# 2_POWER.net
KiCad netlist of a schematic drawn in Altium Designer
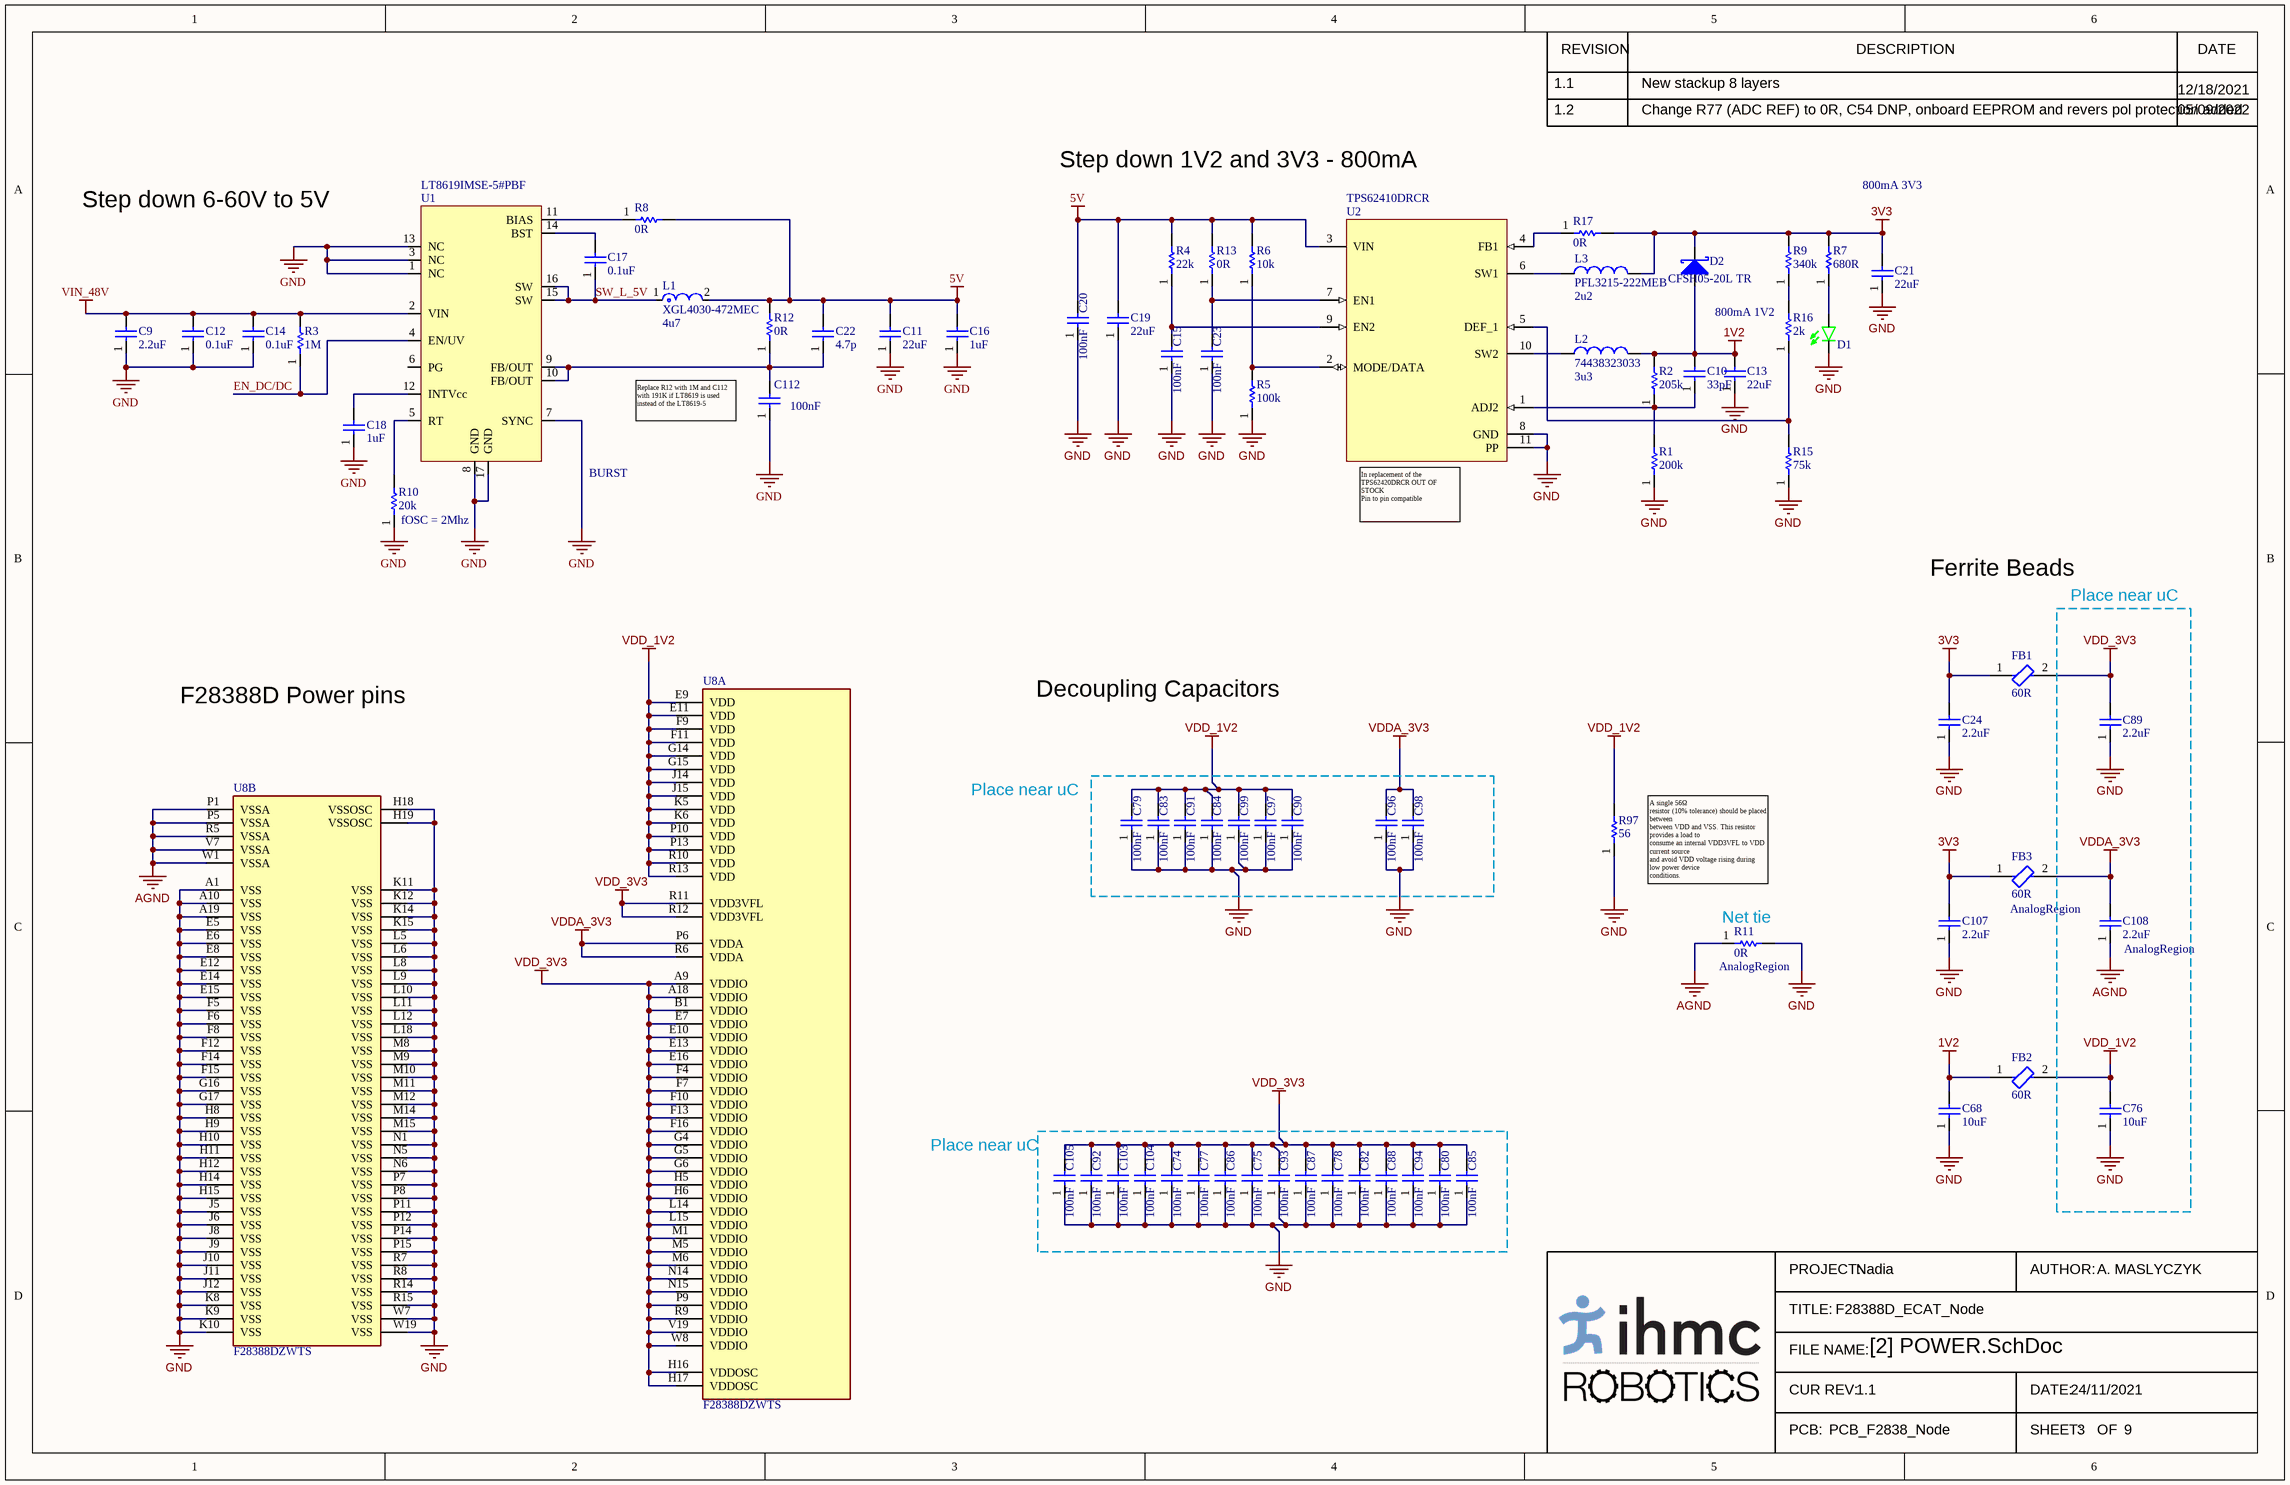
[diagram p0: [2] POWER.SchDoc]

(export (version "E")
  (design (tool "Eeschema 10.0.6"))
  (components
    (comp (ref "C9")
      (value "2.2uF")
      (footprint "CAPC3216X16N(1206)")
      (description "CAP CER 2.2UF 100V X7S 1206")
      (fields (field (name "MPN") "C3216X7S2A225K160AB") (field (name "TOLERANCE") "10%"))
      (libsource (lib "IHMC_Altium_Lib") (part "2.2uF_100V_1206_Cap"))
    )
    (comp (ref "C10")
      (value "33pF")
      (footprint "0402_C")
      (description "Cap, Mlcc, Np0, 33Pf, 25V, 0402 Rohs Compliant: Yes")
      (fields
        (field (name "MANUFACTURER") "Wurth Electronics")
        (field (name "MANUFACTURER PART NUMBER") "885012005043")
      )
      (libsource (lib "IHMC_Altium_Lib") (part "33pF_25V_5%_C0G_0402_885012005043_CAP"))
    )
    (comp (ref "C11")
      (value "22uF")
      (footprint "CAPC1608X09N(0603)")
      (description "CAP CER 22UF 10V X5R 0603")
      (fields (field (name "MPN") "C1608X5R1A226M080AC") (field (name "TOLERANCE") "20%"))
      (libsource (lib "IHMC_Altium_Lib") (part "22uF_10V_0603_CAP"))
    )
    (comp (ref "C12")
      (value "0.1uF")
      (footprint "CAPC1608X09N(0603)")
      (description "CAP CER 0.1UF 100V X7R 0603")
      (fields (field (name "MPN") "CL10B104KC8NNNC") (field (name "TOLERANCE") "10%"))
      (libsource (lib "IHMC_Altium_Lib") (part "0.1uF_100V_0603_CAP"))
    )
    (comp (ref "C13")
      (value "22uF")
      (footprint "CAPC1608X09N(0603)")
      (description "CAP CER 22UF 10V X5R 0603")
      (fields (field (name "MPN") "C1608X5R1A226M080AC") (field (name "TOLERANCE") "20%"))
      (libsource (lib "IHMC_Altium_Lib") (part "22uF_10V_0603_CAP"))
    )
    (comp (ref "C14")
      (value "0.1uF")
      (footprint "CAPC1608X09N(0603)")
      (description "CAP CER 0.1UF 100V X7R 0603")
      (fields (field (name "MPN") "CL10B104KC8NNNC") (field (name "TOLERANCE") "10%"))
      (libsource (lib "IHMC_Altium_Lib") (part "0.1uF_100V_0603_CAP"))
    )
    (comp (ref "C15")
      (value "100nF")
      (footprint "CAPC1005X03N(0402)")
      (description "CAP CER 0.1UF 16V X7R 0402")
      (fields (field (name "MPN") "GRM155R71C104JA88D") (field (name "TOLERANCE") "5%"))
      (libsource (lib "IHMC_Altium_Lib") (part "100nF_16V_0402_CAP"))
    )
    (comp (ref "C16")
      (value "1uF")
      (footprint "CAPC1608X09N(0603)")
      (description "MLCC - SMD/SMT 25volts 1uF X5R 10%")
      (fields
        (field (name "MPN") "C0603C105K3PACTU")
        (field (name "VOLTAGE") "25VDC")
        (field (name "DRAWN BY") "TC")
      )
      (libsource (lib "IHMC_Altium_Lib") (part "1uF_25VDC_0603_Cap"))
    )
    (comp (ref "C17")
      (value "0.1uF")
      (footprint "CAPC1608X09N(0603)")
      (description "CAP CER 0.1UF 100V X7R 0603")
      (fields (field (name "MPN") "CL10B104KC8NNNC") (field (name "TOLERANCE") "10%"))
      (libsource (lib "IHMC_Altium_Lib") (part "0.1uF_100V_0603_CAP"))
    )
    (comp (ref "C18")
      (value "1uF")
      (footprint "CAPC1608X09N(0603)")
      (description "MLCC - SMD/SMT 25volts 1uF X5R 10%")
      (fields
        (field (name "MPN") "C0603C105K3PACTU")
        (field (name "VOLTAGE") "25VDC")
        (field (name "DRAWN BY") "TC")
      )
      (libsource (lib "IHMC_Altium_Lib") (part "1uF_25VDC_0603_Cap"))
    )
    (comp (ref "C19")
      (value "22uF")
      (footprint "CAPC1608X09N(0603)")
      (description "CAP CER 22UF 10V X5R 0603")
      (fields (field (name "MPN") "C1608X5R1A226M080AC") (field (name "TOLERANCE") "20%"))
      (libsource (lib "IHMC_Altium_Lib") (part "22uF_10V_0603_CAP"))
    )
    (comp (ref "C20")
      (value "100nF")
      (footprint "CAPC1005X03N(0402)")
      (description "CAP CER 0.1UF 16V X7R 0402")
      (fields (field (name "MPN") "GRM155R71C104JA88D") (field (name "TOLERANCE") "5%"))
      (libsource (lib "IHMC_Altium_Lib") (part "100nF_16V_0402_CAP"))
    )
    (comp (ref "C21")
      (value "22uF")
      (footprint "CAPC1608X09N(0603)")
      (description "CAP CER 22UF 10V X5R 0603")
      (fields (field (name "MPN") "C1608X5R1A226M080AC") (field (name "TOLERANCE") "20%"))
      (libsource (lib "IHMC_Altium_Lib") (part "22uF_10V_0603_CAP"))
    )
    (comp (ref "C22")
      (value "4.7p")
      (footprint "0402_C")
      (fields
        (field (name "MANUFACTURER") "TDK")
        (field (name "MANUFACTURER PART NUMBER") "CGA2B2C0G1H4R7C050BA")
      )
      (libsource (lib "IHMC_Altium_Lib") (part "4p7_0402_50V_C0G_  CGA2B2C0G1H4R7C050BA"))
    )
    (comp (ref "C23")
      (value "100nF")
      (footprint "CAPC1005X03N(0402)")
      (description "CAP CER 0.1UF 16V X7R 0402")
      (fields (field (name "MPN") "GRM155R71C104JA88D") (field (name "TOLERANCE") "5%"))
      (libsource (lib "IHMC_Altium_Lib") (part "100nF_16V_0402_CAP"))
    )
    (comp (ref "C24")
      (value "2.2uF")
      (footprint "CAPC1608X09N(0603)")
      (description "CAP CER 2.2UF 10V X5R 0603")
      (fields (field (name "MPN") "GRM188R61A225KE34D") (field (name "TOLERANCE") "10%"))
      (libsource (lib "IHMC_Altium_Lib") (part "2.2uF_10V_0603_CAP"))
    )
    (comp (ref "C68")
      (value "10uF")
      (footprint "CAPC1608X09N(0603)")
      (description "CAP CER 10UF 16V X6S 0603")
      (fields (field (name "MPN") "CL10X106MO8NRNC") (field (name "TOLERANCE") "20%"))
      (libsource (lib "IHMC_Altium_Lib") (part "10uF_16V_0603_CAP"))
    )
    (comp (ref "C74")
      (value "100nF")
      (footprint "CAPC1005X03N(0402)")
      (description "CAP CER 0.1UF 16V X7R 0402")
      (fields (field (name "MPN") "GRM155R71C104JA88D") (field (name "TOLERANCE") "5%"))
      (libsource (lib "IHMC_Altium_Lib") (part "100nF_16V_0402_CAP"))
    )
    (comp (ref "C75")
      (value "100nF")
      (footprint "CAPC1005X03N(0402)")
      (description "CAP CER 0.1UF 16V X7R 0402")
      (fields (field (name "MPN") "GRM155R71C104JA88D") (field (name "TOLERANCE") "5%"))
      (libsource (lib "IHMC_Altium_Lib") (part "100nF_16V_0402_CAP"))
    )
    (comp (ref "C76")
      (value "10uF")
      (footprint "CAPC1608X09N(0603)")
      (description "CAP CER 10UF 16V X6S 0603")
      (fields (field (name "MPN") "CL10X106MO8NRNC") (field (name "TOLERANCE") "20%"))
      (libsource (lib "IHMC_Altium_Lib") (part "10uF_16V_0603_CAP"))
    )
    (comp (ref "C77")
      (value "100nF")
      (footprint "CAPC1005X03N(0402)")
      (description "CAP CER 0.1UF 16V X7R 0402")
      (fields (field (name "MPN") "GRM155R71C104JA88D") (field (name "TOLERANCE") "5%"))
      (libsource (lib "IHMC_Altium_Lib") (part "100nF_16V_0402_CAP"))
    )
    (comp (ref "C78")
      (value "100nF")
      (footprint "CAPC1005X03N(0402)")
      (description "CAP CER 0.1UF 16V X7R 0402")
      (fields (field (name "MPN") "GRM155R71C104JA88D") (field (name "TOLERANCE") "5%"))
      (libsource (lib "IHMC_Altium_Lib") (part "100nF_16V_0402_CAP"))
    )
    (comp (ref "C79")
      (value "100nF")
      (footprint "CAPC1005X03N(0402)")
      (description "CAP CER 0.1UF 16V X7R 0402")
      (fields (field (name "MPN") "GRM155R71C104JA88D") (field (name "TOLERANCE") "5%"))
      (libsource (lib "IHMC_Altium_Lib") (part "100nF_16V_0402_CAP"))
    )
    (comp (ref "C80")
      (value "100nF")
      (footprint "CAPC1005X03N(0402)")
      (description "CAP CER 0.1UF 16V X7R 0402")
      (fields (field (name "MPN") "GRM155R71C104JA88D") (field (name "TOLERANCE") "5%"))
      (libsource (lib "IHMC_Altium_Lib") (part "100nF_16V_0402_CAP"))
    )
    (comp (ref "C82")
      (value "100nF")
      (footprint "CAPC1005X03N(0402)")
      (description "CAP CER 0.1UF 16V X7R 0402")
      (fields (field (name "MPN") "GRM155R71C104JA88D") (field (name "TOLERANCE") "5%"))
      (libsource (lib "IHMC_Altium_Lib") (part "100nF_16V_0402_CAP"))
    )
    (comp (ref "C83")
      (value "100nF")
      (footprint "CAPC1005X03N(0402)")
      (description "CAP CER 0.1UF 16V X7R 0402")
      (fields (field (name "MPN") "GRM155R71C104JA88D") (field (name "TOLERANCE") "5%"))
      (libsource (lib "IHMC_Altium_Lib") (part "100nF_16V_0402_CAP"))
    )
    (comp (ref "C84")
      (value "100nF")
      (footprint "CAPC1005X03N(0402)")
      (description "CAP CER 0.1UF 16V X7R 0402")
      (fields (field (name "MPN") "GRM155R71C104JA88D") (field (name "TOLERANCE") "5%"))
      (libsource (lib "IHMC_Altium_Lib") (part "100nF_16V_0402_CAP"))
    )
    (comp (ref "C85")
      (value "100nF")
      (footprint "CAPC1005X03N(0402)")
      (description "CAP CER 0.1UF 16V X7R 0402")
      (fields (field (name "MPN") "GRM155R71C104JA88D") (field (name "TOLERANCE") "5%"))
      (libsource (lib "IHMC_Altium_Lib") (part "100nF_16V_0402_CAP"))
    )
    (comp (ref "C86")
      (value "100nF")
      (footprint "CAPC1005X03N(0402)")
      (description "CAP CER 0.1UF 16V X7R 0402")
      (fields (field (name "MPN") "GRM155R71C104JA88D") (field (name "TOLERANCE") "5%"))
      (libsource (lib "IHMC_Altium_Lib") (part "100nF_16V_0402_CAP"))
    )
    (comp (ref "C87")
      (value "100nF")
      (footprint "CAPC1005X03N(0402)")
      (description "CAP CER 0.1UF 16V X7R 0402")
      (fields (field (name "MPN") "GRM155R71C104JA88D") (field (name "TOLERANCE") "5%"))
      (libsource (lib "IHMC_Altium_Lib") (part "100nF_16V_0402_CAP"))
    )
    (comp (ref "C88")
      (value "100nF")
      (footprint "CAPC1005X03N(0402)")
      (description "CAP CER 0.1UF 16V X7R 0402")
      (fields (field (name "MPN") "GRM155R71C104JA88D") (field (name "TOLERANCE") "5%"))
      (libsource (lib "IHMC_Altium_Lib") (part "100nF_16V_0402_CAP"))
    )
    (comp (ref "C89")
      (value "2.2uF")
      (footprint "CAPC1608X09N(0603)")
      (description "CAP CER 2.2UF 10V X5R 0603")
      (fields (field (name "MPN") "GRM188R61A225KE34D") (field (name "TOLERANCE") "10%"))
      (libsource (lib "IHMC_Altium_Lib") (part "2.2uF_10V_0603_CAP"))
    )
    (comp (ref "C90")
      (value "100nF")
      (footprint "CAPC1005X03N(0402)")
      (description "CAP CER 0.1UF 16V X7R 0402")
      (fields (field (name "MPN") "GRM155R71C104JA88D") (field (name "TOLERANCE") "5%"))
      (libsource (lib "IHMC_Altium_Lib") (part "100nF_16V_0402_CAP"))
    )
    (comp (ref "C91")
      (value "100nF")
      (footprint "CAPC1005X03N(0402)")
      (description "CAP CER 0.1UF 16V X7R 0402")
      (fields (field (name "MPN") "GRM155R71C104JA88D") (field (name "TOLERANCE") "5%"))
      (libsource (lib "IHMC_Altium_Lib") (part "100nF_16V_0402_CAP"))
    )
    (comp (ref "C92")
      (value "100nF")
      (footprint "CAPC1005X03N(0402)")
      (description "CAP CER 0.1UF 16V X7R 0402")
      (fields (field (name "MPN") "GRM155R71C104JA88D") (field (name "TOLERANCE") "5%"))
      (libsource (lib "IHMC_Altium_Lib") (part "100nF_16V_0402_CAP"))
    )
    (comp (ref "C93")
      (value "100nF")
      (footprint "CAPC1005X03N(0402)")
      (description "CAP CER 0.1UF 16V X7R 0402")
      (fields (field (name "MPN") "GRM155R71C104JA88D") (field (name "TOLERANCE") "5%"))
      (libsource (lib "IHMC_Altium_Lib") (part "100nF_16V_0402_CAP"))
    )
    (comp (ref "C94")
      (value "100nF")
      (footprint "CAPC1005X03N(0402)")
      (description "CAP CER 0.1UF 16V X7R 0402")
      (fields (field (name "MPN") "GRM155R71C104JA88D") (field (name "TOLERANCE") "5%"))
      (libsource (lib "IHMC_Altium_Lib") (part "100nF_16V_0402_CAP"))
    )
    (comp (ref "C96")
      (value "100nF")
      (footprint "CAPC1005X03N(0402)")
      (description "CAP CER 0.1UF 16V X7R 0402")
      (fields (field (name "MPN") "GRM155R71C104JA88D") (field (name "TOLERANCE") "5%"))
      (libsource (lib "IHMC_Altium_Lib") (part "100nF_16V_0402_CAP"))
    )
    (comp (ref "C97")
      (value "100nF")
      (footprint "CAPC1005X03N(0402)")
      (description "CAP CER 0.1UF 16V X7R 0402")
      (fields (field (name "MPN") "GRM155R71C104JA88D") (field (name "TOLERANCE") "5%"))
      (libsource (lib "IHMC_Altium_Lib") (part "100nF_16V_0402_CAP"))
    )
    (comp (ref "C98")
      (value "100nF")
      (footprint "CAPC1005X03N(0402)")
      (description "CAP CER 0.1UF 16V X7R 0402")
      (fields (field (name "MPN") "GRM155R71C104JA88D") (field (name "TOLERANCE") "5%"))
      (libsource (lib "IHMC_Altium_Lib") (part "100nF_16V_0402_CAP"))
    )
    (comp (ref "C99")
      (value "100nF")
      (footprint "CAPC1005X03N(0402)")
      (description "CAP CER 0.1UF 16V X7R 0402")
      (fields (field (name "MPN") "GRM155R71C104JA88D") (field (name "TOLERANCE") "5%"))
      (libsource (lib "IHMC_Altium_Lib") (part "100nF_16V_0402_CAP"))
    )
    (comp (ref "C103")
      (value "100nF")
      (footprint "CAPC1005X03N(0402)")
      (description "CAP CER 0.1UF 16V X7R 0402")
      (fields (field (name "MPN") "GRM155R71C104JA88D") (field (name "TOLERANCE") "5%"))
      (libsource (lib "IHMC_Altium_Lib") (part "100nF_16V_0402_CAP"))
    )
    (comp (ref "C104")
      (value "100nF")
      (footprint "CAPC1005X03N(0402)")
      (description "CAP CER 0.1UF 16V X7R 0402")
      (fields (field (name "MPN") "GRM155R71C104JA88D") (field (name "TOLERANCE") "5%"))
      (libsource (lib "IHMC_Altium_Lib") (part "100nF_16V_0402_CAP"))
    )
    (comp (ref "C105")
      (value "100nF")
      (footprint "CAPC1005X03N(0402)")
      (description "CAP CER 0.1UF 16V X7R 0402")
      (fields (field (name "MPN") "GRM155R71C104JA88D") (field (name "TOLERANCE") "5%"))
      (libsource (lib "IHMC_Altium_Lib") (part "100nF_16V_0402_CAP"))
    )
    (comp (ref "C107")
      (value "2.2uF")
      (footprint "CAPC1608X09N(0603)")
      (description "CAP CER 2.2UF 10V X5R 0603")
      (fields (field (name "MPN") "GRM188R61A225KE34D") (field (name "TOLERANCE") "10%"))
      (libsource (lib "IHMC_Altium_Lib") (part "2.2uF_10V_0603_CAP"))
    )
    (comp (ref "C108")
      (value "2.2uF")
      (footprint "CAPC1608X09N(0603)")
      (description "CAP CER 2.2UF 10V X5R 0603")
      (fields
        (field (name "MPN") "GRM188R61A225KE34D")
        (field (name "TOLERANCE") "10%")
        (field (name "CLASSNAME") "AnalogRegion")
      )
      (libsource (lib "IHMC_Altium_Lib") (part "2.2uF_10V_0603_CAP"))
    )
    (comp (ref "C112")
      (value "100nF")
      (footprint "CAPC1005X03N(0402)")
      (description "CAP CER 0.1UF 16V X7R 0402")
      (fields (field (name "TOLERANCE") "5%") (field (name "MPN") "GRM155R71C104JA88D"))
      (libsource (lib "IHMC_Altium_Lib") (part "100nF_16V_0402_CAP"))
    )
    (comp (ref "D1")
      (value "LTST-C193KGKT-5A")
      (footprint "LEDC1608X07N(0603)")
      (description "LED GREEN CLEAR CHIP SMD")
      (fields (field (name "DRAWN BY") "TC"))
      (libsource (lib "IHMC_Altium_Lib") (part "GREEN_LED_0603"))
    )
    (comp (ref "D2")
      (value "CFSH05-20L TR")
      (footprint "SOD-882")
      (description "Silicon SCHOTTKY Diode Low Forward Voltage 20V 3A 2-Pin SOD-882L Surface Mount T/R")
      (fields (field (name "MANUFACTURER") "Central Semiconductor"))
      (libsource (lib "IHMC_Altium_Lib") (part "CFSH05-20L TR_SCHOTTKY_20V_500mA_SOD882_DIODE"))
    )
    (comp (ref "FB1")
      (value "BKP2125HS600-T")
      (footprint "FP-BKP2125-IPC_C")
      (fields
        (field (name "TOLERANCE") "25%")
        (field (name "MANUFACTURER") "Taiyo Yuden")
        (field (name "IMPEDANCE") "60R")
      )
      (libsource (lib "IHMC_Altium_Lib") (part "60R_100Mhz_0805_3A"))
    )
    (comp (ref "FB2")
      (value "BKP2125HS600-T")
      (footprint "FP-BKP2125-IPC_C")
      (fields
        (field (name "TOLERANCE") "25%")
        (field (name "MANUFACTURER") "Taiyo Yuden")
        (field (name "IMPEDANCE") "60R")
      )
      (libsource (lib "IHMC_Altium_Lib") (part "60R_100Mhz_0805_3A"))
    )
    (comp (ref "FB3")
      (value "BKP2125HS600-T")
      (footprint "FP-BKP2125-IPC_C")
      (fields
        (field (name "TOLERANCE") "25%")
        (field (name "MANUFACTURER") "Taiyo Yuden")
        (field (name "IMPEDANCE") "60R")
        (field (name "CLASSNAME") "AnalogRegion")
      )
      (libsource (lib "IHMC_Altium_Lib") (part "60R_100Mhz_0805_3A"))
    )
    (comp (ref "L1")
      (value "XGL4030-472MEC")
      (footprint "FP-XGL4030-472MEC-MFG")
      (description "Inductor Power Shielded Wirewound 4.7uH 20% 1MHz Composite 6.6A 31.5mOhm DCR Automotive T/R")
      (fields (field (name "ALTIUM_VALUE") "4u7") (field (name "MPN") "XGL4030-472"))
      (libsource (lib "IHMC_Altium_Lib") (part "XGL4030-472MEC_4u7_2A1_IND"))
    )
    (comp (ref "L2")
      (value "74438323033")
      (footprint "SMD 2510")
      (description "Inductor Power Shielded Wirewound 3.3uH 20% 100KHz Powdered Iron 1.25A 264mOhm DCR 1008 T/R")
      (fields
        (field (name "MANUFACTURER") "Wurth Electronics")
        (field (name "TOLERANCE") "20%")
        (field (name "ALTIUM_VALUE") "3u3")
      )
      (libsource (lib "IHMC_Altium_Lib") (part "3.3uH_1.25A_2520_IND"))
    )
    (comp (ref "L3")
      (value "PFL3215-222MEB")
      (footprint "1206_L")
      (description "Power inductor, shielded, 20% tol, SMT, RoHS, halogen-f")
      (fields
        (field (name "MANUFACTURER") "Coilcraft")
        (field (name "TOLERANCE") "20%")
        (field (name "ALTIUM_VALUE") "2u2")
      )
      (libsource (lib "IHMC_Altium_Lib") (part "2.2uH_1.4A_1206_PFL3215-222MEB_IND"))
    )
    (comp (ref "R1")
      (value "200k")
      (footprint "0402")
      (description "Res Thick Film 0402 200K Ohm 1% 1/10W ±100ppm/¦C SMD Punched Carrier T/R")
      (fields
        (field (name "MANUFACTURER") "Panasonic")
        (field (name "MANUFACTURER PART NUMBER") "ERJ-2RKF2003X")
      )
      (libsource (lib "IHMC_Altium_Lib") (part "200k_0402_1%_ERJ-2RKF2003X_RES"))
    )
    (comp (ref "R2")
      (value "205k")
      (footprint "0402")
      (description "Res Thick Film 0402 205K Ohm 1% 1/16W ±100ppm/°C Molded SMD SMD Paper T/R")
      (fields
        (field (name "MANUFACTURER") "Vishay")
        (field (name "MANUFACTURER PART NUMBER") "CRCW0402205KFKED")
      )
      (libsource (lib "IHMC_Altium_Lib") (part "205k_0402_1%_CRCW0402205KFKED_RES"))
    )
    (comp (ref "R3")
      (value "1M")
      (footprint "RESC1608X09N(0603)")
      (description "RES SMD 1M OHM 1% 1/10W 0603")
      (fields (field (name "MPN") "RC0603FR-071ML") (field (name "TOLERANCE") "1%"))
      (libsource (lib "IHMC_Altium_Lib") (part "1M_1/10W_RES_0603"))
    )
    (comp (ref "R4")
      (value "22k")
      (footprint "0402")
      (description "Res Thick Film 0402 22K Ohm 5% 1/16W ±200ppm/°C Molded SMD SMD Paper T/R")
      (fields
        (field (name "MANUFACTURER") "Vishay Dale")
        (field (name "MANUFACTURER PART NUMBER") "CRCW040222K0JNED")
      )
      (libsource (lib "IHMC_Altium_Lib") (part "22k_5%_0402_CRCW040222K0JNED_RES"))
    )
    (comp (ref "R5")
      (value "100k")
      (footprint "RESC1608X09N(0603)")
      (description "Res Thick Film 0603 100K Ohm 1% 0.1W(1/10W) ±100ppm/C Pad SMD Automotive T/R")
      (fields (field (name "MPN") "ERJ-3EKF1003V") (field (name "TOLERANCE") "1%"))
      (libsource (lib "IHMC_Altium_Lib") (part "100k_1/10W_0603_RES_1"))
    )
    (comp (ref "R6")
      (value "10k")
      (footprint "RESC1005X06N(0402)")
      (description "RES SMD 10K OHM 1% 1/16W 0402")
      (fields (field (name "TOLERANCE") "1%") (field (name "POWER") "1/16W"))
      (libsource (lib "IHMC_Altium_Lib") (part "10k_1/16W_0402_RES"))
    )
    (comp (ref "R7")
      (value "680R")
      (footprint "RESC1608X09N(0603)")
      (description "RES SMD 680 OHM 1% 1/10W 0603")
      (fields (field (name "MPN") "RC0603FR-07680RL") (field (name "TOLERANCE") "1%"))
      (libsource (lib "IHMC_Altium_Lib") (part "680R_1/10W_0603_RES"))
    )
    (comp (ref "R8")
      (value "0R")
      (footprint "RESC1608X09N(0603)")
      (description "RES SMD 0 OHM JUMPER 1/10W 0603")
      (fields (field (name "MPN") "RC0603JR-070RL") (field (name "TOLERANCE") "Jumper"))
      (libsource (lib "IHMC_Altium_Lib") (part "0R_1/10W_0603_RES"))
    )
    (comp (ref "R9")
      (value "340k")
      (footprint "0402")
      (description "Res Thick Film 0402 340K Ohm 1% 1/16W ±100ppm/°C Molded SMD SMD Paper T/R")
      (fields
        (field (name "MANUFACTURER") "Vishay")
        (field (name "MANUFACTURER PART NUMBER") "CRCW0402340KFKED")
      )
      (libsource (lib "IHMC_Altium_Lib") (part "340k_1%_0402_CRCW0402340KFKED_RES"))
    )
    (comp (ref "R10")
      (value "20k")
      (footprint "0402")
      (description "RES SMD 20K OHM 1% 1/10W 0402")
      (fields
        (field (name "MANUFACTURER") "Panasonic")
        (field (name "MANUFACTURER PART NUMBER") "ERJ-2RKF2002X")
      )
      (libsource (lib "IHMC_Altium_Lib") (part "20K_0402_1%_ERJ-2RKF2002X_RES"))
    )
    (comp (ref "R11")
      (value "0R")
      (footprint "0402")
      (fields
        (field (name "MANUFACTURER") "Vishay Dale")
        (field (name "MANUFACTURER PART NUMBER") "RCS04020000Z0ED")
        (field (name "CLASSNAME") "AnalogRegion")
      )
      (libsource (lib "IHMC_Altium_Lib") (part "0R_1/5W_0402_RCS04020000Z0ED_RES"))
    )
    (comp (ref "R12")
      (value "0R")
      (footprint "RESC1608X09N(0603)")
      (description "RES SMD 0 OHM JUMPER 1/10W 0603")
      (fields (field (name "MPN") "RC0603JR-070RL") (field (name "TOLERANCE") "Jumper"))
      (libsource (lib "IHMC_Altium_Lib") (part "0R_1/10W_0603_RES"))
    )
    (comp (ref "R13")
      (value "0R")
      (footprint "0402")
      (fields
        (field (name "MANUFACTURER") "Vishay Dale")
        (field (name "MANUFACTURER PART NUMBER") "RCS04020000Z0ED")
      )
      (libsource (lib "IHMC_Altium_Lib") (part "0R_1/5W_0402_RCS04020000Z0ED_RES"))
    )
    (comp (ref "R15")
      (value "75k")
      (footprint "0603")
      (description "Res Thin Film 0603 75K Ohm 0.5% 1/10W ±50ppm/°C Molded SMD SMD Paper T/R")
      (fields
        (field (name "MANUFACTURER") "Yageo")
        (field (name "MANUFACTURER PART NUMBER") "RT0603DRE0775KL")
      )
      (libsource (lib "IHMC_Altium_Lib") (part "75k_0.5%_0603_RT0603DRE0775KL_RES"))
    )
    (comp (ref "R16")
      (value "2k")
      (footprint "RESC1005X06N(0402)")
      (description "RES SMD 2K OHM 1% 1/16W 0402")
      (fields (field (name "MPN") "RC0402FR-072KL") (field (name "POWER") "1/16W"))
      (libsource (lib "IHMC_Altium_Lib") (part "2k_1/16_0402_RES"))
    )
    (comp (ref "R17")
      (value "0R")
      (footprint "RESC1608X09N(0603)")
      (description "RES SMD 0 OHM JUMPER 1/10W 0603")
      (fields (field (name "MPN") "RC0603JR-070RL") (field (name "TOLERANCE") "Jumper"))
      (libsource (lib "IHMC_Altium_Lib") (part "0R_1/10W_0603_RES"))
    )
    (comp (ref "R97")
      (value "56")
      (footprint "0402")
      (description "RES SMD 56 OHM 5% 1/16W 0402")
      (fields
        (field (name "MANUFACTURER") "Vishay Dale")
        (field (name "MANUFACTURER PART NUMBER") "CRCW040256R0JNED")
      )
      (libsource (lib "IHMC_Altium_Lib") (part "56R_1/16W_0402_RES_CRCW040256R0JNED"))
    )
    (comp (ref "U1")
      (value "LT8619IMSE-5#PBF")
      (footprint "SOP50P490X110-17N")
      (description "LT8619 - 60V, 1.2A Synchronous Monolithic Buck Regulator with 6µA Quiescent Current")
      (fields (field (name "MANUFACTURER") "Analog Devices / Linear Technology"))
      (libsource (lib "IHMC_Altium_Lib") (part "LT8619_BUCK_5V_1.2A"))
    )
    (comp (ref "U2")
      (value "TPS62410DRCR")
      (footprint "DRC0010J_V - 3vias")
      (description "TPS62410 2.25MHZ 2X800MA Dual St")
      (fields (field (name "MANUFACTURER") "Texas Instruments"))
      (libsource (lib "IHMC_Altium_Lib") (part "TPS62410DRCR_DUAL_BUCK"))
    )
    (comp (ref "U8")
      (value "F28388DZWTS")
      (footprint "FP-ZWT0337A-IPC_B - ESNACK")
      (fields
        (field (name "MANUFACTURER") "Texas instruments")
        (field (name "OCTOPART") "https://octopart.com/f28388dzwts-texas+instruments-102550657")
      )
      (libsource (lib "IHMC_IC") (part "TMS320F28388D_32bit_uC"))
    )
  )
  (nets
    (net (code "1") (name "/EN_DC{slash}DC") (class "Default")
      (node (ref "R3") (pin "1") (pinfunction "1_1") (pintype "passive"))
      (node (ref "U1") (pin "4") (pinfunction "EN/UV_4") (pintype "passive"))
    )
    (net (code "2") (name "/SW_L_5V") (class "Default")
      (node (ref "C17") (pin "1") (pinfunction "1_1") (pintype "passive"))
      (node (ref "L1") (pin "1") (pinfunction "1_1") (pintype "passive"))
      (node (ref "U1") (pin "15") (pinfunction "SW_15") (pintype "passive"))
      (node (ref "U1") (pin "16") (pinfunction "SW_16") (pintype "passive"))
    )
    (net (code "3") (name "1V2") (class "Default")
      (node (ref "C10") (pin "2") (pinfunction "2_2") (pintype "passive"))
      (node (ref "C13") (pin "2") (pinfunction "2_2") (pintype "passive"))
      (node (ref "C68") (pin "2") (pinfunction "2_2") (pintype "passive"))
      (node (ref "D2") (pin "2") (pinfunction "A_2") (pintype "passive"))
      (node (ref "FB2") (pin "1") (pinfunction "1_1") (pintype "passive"))
      (node (ref "L2") (pin "2") (pinfunction "2_2") (pintype "passive"))
      (node (ref "R2") (pin "2") (pinfunction "2_2") (pintype "passive"))
    )
    (net (code "4") (name "3V3") (class "Default")
      (node (ref "C107") (pin "2") (pinfunction "2_2") (pintype "passive"))
      (node (ref "C21") (pin "2") (pinfunction "2_2") (pintype "passive"))
      (node (ref "C24") (pin "2") (pinfunction "2_2") (pintype "passive"))
      (node (ref "D2") (pin "1") (pinfunction "K_1") (pintype "passive"))
      (node (ref "FB1") (pin "1") (pinfunction "1_1") (pintype "passive"))
      (node (ref "FB3") (pin "1") (pinfunction "1_1") (pintype "passive"))
      (node (ref "L3") (pin "2") (pinfunction "2_2") (pintype "passive"))
      (node (ref "R17") (pin "2") (pinfunction "2_2") (pintype "passive"))
      (node (ref "R7") (pin "2") (pinfunction "2_2") (pintype "passive"))
      (node (ref "R9") (pin "2") (pinfunction "2_2") (pintype "passive"))
    )
    (net (code "5") (name "5V") (class "Default")
      (node (ref "C11") (pin "2") (pinfunction "2_2") (pintype "passive"))
      (node (ref "C16") (pin "2") (pinfunction "2_2") (pintype "passive"))
      (node (ref "C19") (pin "2") (pinfunction "2_2") (pintype "passive"))
      (node (ref "C20") (pin "2") (pinfunction "2_2") (pintype "passive"))
      (node (ref "C22") (pin "2") (pinfunction "2_2") (pintype "passive"))
      (node (ref "L1") (pin "2") (pinfunction "2_2") (pintype "passive"))
      (node (ref "R12") (pin "2") (pinfunction "2_2") (pintype "passive"))
      (node (ref "R13") (pin "2") (pinfunction "2_2") (pintype "passive"))
      (node (ref "R4") (pin "2") (pinfunction "2_2") (pintype "passive"))
      (node (ref "R6") (pin "2") (pinfunction "2_2") (pintype "passive"))
      (node (ref "R8") (pin "2") (pinfunction "2_2") (pintype "passive"))
      (node (ref "U2") (pin "3") (pinfunction "VIN_3") (pintype "power_in"))
    )
    (net (code "6") (name "AGND") (class "Default")
      (node (ref "C108") (pin "1") (pinfunction "1_1") (pintype "passive"))
      (node (ref "R11") (pin "1") (pinfunction "1_1") (pintype "passive"))
      (node (ref "U8") (pin "P1") (pinfunction "VSSA_P1") (pintype "power_in"))
      (node (ref "U8") (pin "P5") (pinfunction "VSSA_P5") (pintype "power_in"))
      (node (ref "U8") (pin "R5") (pinfunction "VSSA_R5") (pintype "power_in"))
      (node (ref "U8") (pin "V7") (pinfunction "VSSA_V7") (pintype "power_in"))
      (node (ref "U8") (pin "W1") (pinfunction "VSSA_W1") (pintype "power_in"))
    )
    (net (code "7") (name "GND") (class "Default")
      (node (ref "C103") (pin "1") (pinfunction "1_1") (pintype "passive"))
      (node (ref "C104") (pin "1") (pinfunction "1_1") (pintype "passive"))
      (node (ref "C105") (pin "1") (pinfunction "1_1") (pintype "passive"))
      (node (ref "C107") (pin "1") (pinfunction "1_1") (pintype "passive"))
      (node (ref "C11") (pin "1") (pinfunction "1_1") (pintype "passive"))
      (node (ref "C112") (pin "1") (pinfunction "1_1") (pintype "passive"))
      (node (ref "C12") (pin "1") (pinfunction "1_1") (pintype "passive"))
      (node (ref "C13") (pin "1") (pinfunction "1_1") (pintype "passive"))
      (node (ref "C14") (pin "1") (pinfunction "1_1") (pintype "passive"))
      (node (ref "C15") (pin "1") (pinfunction "1_1") (pintype "passive"))
      (node (ref "C16") (pin "1") (pinfunction "1_1") (pintype "passive"))
      (node (ref "C18") (pin "1") (pinfunction "1_1") (pintype "passive"))
      (node (ref "C19") (pin "1") (pinfunction "1_1") (pintype "passive"))
      (node (ref "C20") (pin "1") (pinfunction "1_1") (pintype "passive"))
      (node (ref "C21") (pin "1") (pinfunction "1_1") (pintype "passive"))
      (node (ref "C23") (pin "1") (pinfunction "1_1") (pintype "passive"))
      (node (ref "C24") (pin "1") (pinfunction "1_1") (pintype "passive"))
      (node (ref "C68") (pin "1") (pinfunction "1_1") (pintype "passive"))
      (node (ref "C74") (pin "1") (pinfunction "1_1") (pintype "passive"))
      (node (ref "C75") (pin "1") (pinfunction "1_1") (pintype "passive"))
      (node (ref "C76") (pin "1") (pinfunction "1_1") (pintype "passive"))
      (node (ref "C77") (pin "1") (pinfunction "1_1") (pintype "passive"))
      (node (ref "C78") (pin "1") (pinfunction "1_1") (pintype "passive"))
      (node (ref "C79") (pin "1") (pinfunction "1_1") (pintype "passive"))
      (node (ref "C80") (pin "1") (pinfunction "1_1") (pintype "passive"))
      (node (ref "C82") (pin "1") (pinfunction "1_1") (pintype "passive"))
      (node (ref "C83") (pin "1") (pinfunction "1_1") (pintype "passive"))
      (node (ref "C84") (pin "1") (pinfunction "1_1") (pintype "passive"))
      (node (ref "C85") (pin "1") (pinfunction "1_1") (pintype "passive"))
      (node (ref "C86") (pin "1") (pinfunction "1_1") (pintype "passive"))
      (node (ref "C87") (pin "1") (pinfunction "1_1") (pintype "passive"))
      (node (ref "C88") (pin "1") (pinfunction "1_1") (pintype "passive"))
      (node (ref "C89") (pin "1") (pinfunction "1_1") (pintype "passive"))
      (node (ref "C9") (pin "1") (pinfunction "1_1") (pintype "passive"))
      (node (ref "C90") (pin "1") (pinfunction "1_1") (pintype "passive"))
      (node (ref "C91") (pin "1") (pinfunction "1_1") (pintype "passive"))
      (node (ref "C92") (pin "1") (pinfunction "1_1") (pintype "passive"))
      (node (ref "C93") (pin "1") (pinfunction "1_1") (pintype "passive"))
      (node (ref "C94") (pin "1") (pinfunction "1_1") (pintype "passive"))
      (node (ref "C96") (pin "1") (pinfunction "1_1") (pintype "passive"))
      (node (ref "C97") (pin "1") (pinfunction "1_1") (pintype "passive"))
      (node (ref "C98") (pin "1") (pinfunction "1_1") (pintype "passive"))
      (node (ref "C99") (pin "1") (pinfunction "1_1") (pintype "passive"))
      (node (ref "D1") (pin "C") (pinfunction "C_C") (pintype "passive"))
      (node (ref "R1") (pin "1") (pinfunction "1_1") (pintype "passive"))
      (node (ref "R10") (pin "1") (pinfunction "1_1") (pintype "passive"))
      (node (ref "R11") (pin "2") (pinfunction "2_2") (pintype "passive"))
      (node (ref "R15") (pin "1") (pinfunction "1_1") (pintype "passive"))
      (node (ref "R5") (pin "1") (pinfunction "1_1") (pintype "passive"))
      (node (ref "R97") (pin "1") (pinfunction "1_1") (pintype "passive"))
      (node (ref "U1") (pin "1") (pinfunction "NC_1") (pintype "passive"))
      (node (ref "U1") (pin "13") (pinfunction "NC_13") (pintype "passive"))
      (node (ref "U1") (pin "17") (pinfunction "GND_17") (pintype "passive"))
      (node (ref "U1") (pin "3") (pinfunction "NC_3") (pintype "passive"))
      (node (ref "U1") (pin "7") (pinfunction "SYNC_7") (pintype "passive"))
      (node (ref "U1") (pin "8") (pinfunction "GND_8") (pintype "passive"))
      (node (ref "U2") (pin "11") (pinfunction "PP_11") (pintype "power_in"))
      (node (ref "U2") (pin "8") (pinfunction "GND_8") (pintype "power_in"))
      (node (ref "U8") (pin "A1") (pinfunction "VSS_A1") (pintype "power_in"))
      (node (ref "U8") (pin "A10") (pinfunction "VSS_A10") (pintype "power_in"))
      (node (ref "U8") (pin "A19") (pinfunction "VSS_A19") (pintype "power_in"))
      (node (ref "U8") (pin "E12") (pinfunction "VSS_E12") (pintype "power_in"))
      (node (ref "U8") (pin "E14") (pinfunction "VSS_E14") (pintype "power_in"))
      (node (ref "U8") (pin "E15") (pinfunction "VSS_E15") (pintype "power_in"))
      (node (ref "U8") (pin "E5") (pinfunction "VSS_E5") (pintype "power_in"))
      (node (ref "U8") (pin "E6") (pinfunction "VSS_E6") (pintype "power_in"))
      (node (ref "U8") (pin "E8") (pinfunction "VSS_E8") (pintype "power_in"))
      (node (ref "U8") (pin "F12") (pinfunction "VSS_F12") (pintype "power_in"))
      (node (ref "U8") (pin "F14") (pinfunction "VSS_F14") (pintype "power_in"))
      (node (ref "U8") (pin "F15") (pinfunction "VSS_F15") (pintype "power_in"))
      (node (ref "U8") (pin "F5") (pinfunction "VSS_F5") (pintype "power_in"))
      (node (ref "U8") (pin "F6") (pinfunction "VSS_F6") (pintype "power_in"))
      (node (ref "U8") (pin "F8") (pinfunction "VSS_F8") (pintype "power_in"))
      (node (ref "U8") (pin "G16") (pinfunction "VSS_G16") (pintype "power_in"))
      (node (ref "U8") (pin "G17") (pinfunction "VSS_G17") (pintype "power_in"))
      (node (ref "U8") (pin "H10") (pinfunction "VSS_H10") (pintype "power_in"))
      (node (ref "U8") (pin "H11") (pinfunction "VSS_H11") (pintype "power_in"))
      (node (ref "U8") (pin "H12") (pinfunction "VSS_H12") (pintype "power_in"))
      (node (ref "U8") (pin "H14") (pinfunction "VSS_H14") (pintype "power_in"))
      (node (ref "U8") (pin "H15") (pinfunction "VSS_H15") (pintype "power_in"))
      (node (ref "U8") (pin "H18") (pinfunction "VSSOSC_H18") (pintype "power_in"))
      (node (ref "U8") (pin "H19") (pinfunction "VSSOSC_H19") (pintype "power_in"))
      (node (ref "U8") (pin "H8") (pinfunction "VSS_H8") (pintype "power_in"))
      (node (ref "U8") (pin "H9") (pinfunction "VSS_H9") (pintype "power_in"))
      (node (ref "U8") (pin "J10") (pinfunction "VSS_J10") (pintype "power_in"))
      (node (ref "U8") (pin "J11") (pinfunction "VSS_J11") (pintype "power_in"))
      (node (ref "U8") (pin "J12") (pinfunction "VSS_J12") (pintype "power_in"))
      (node (ref "U8") (pin "J5") (pinfunction "VSS_J5") (pintype "power_in"))
      (node (ref "U8") (pin "J6") (pinfunction "VSS_J6") (pintype "power_in"))
      (node (ref "U8") (pin "J8") (pinfunction "VSS_J8") (pintype "power_in"))
      (node (ref "U8") (pin "J9") (pinfunction "VSS_J9") (pintype "power_in"))
      (node (ref "U8") (pin "K10") (pinfunction "VSS_K10") (pintype "power_in"))
      (node (ref "U8") (pin "K11") (pinfunction "VSS_K11") (pintype "power_in"))
      (node (ref "U8") (pin "K12") (pinfunction "VSS_K12") (pintype "power_in"))
      (node (ref "U8") (pin "K14") (pinfunction "VSS_K14") (pintype "power_in"))
      (node (ref "U8") (pin "K15") (pinfunction "VSS_K15") (pintype "power_in"))
      (node (ref "U8") (pin "K8") (pinfunction "VSS_K8") (pintype "power_in"))
      (node (ref "U8") (pin "K9") (pinfunction "VSS_K9") (pintype "power_in"))
      (node (ref "U8") (pin "L10") (pinfunction "VSS_L10") (pintype "power_in"))
      (node (ref "U8") (pin "L11") (pinfunction "VSS_L11") (pintype "power_in"))
      (node (ref "U8") (pin "L12") (pinfunction "VSS_L12") (pintype "power_in"))
      (node (ref "U8") (pin "L18") (pinfunction "VSS_L18") (pintype "power_in"))
      (node (ref "U8") (pin "L5") (pinfunction "VSS_L5") (pintype "power_in"))
      (node (ref "U8") (pin "L6") (pinfunction "VSS_L6") (pintype "power_in"))
      (node (ref "U8") (pin "L8") (pinfunction "VSS_L8") (pintype "power_in"))
      (node (ref "U8") (pin "L9") (pinfunction "VSS_L9") (pintype "power_in"))
      (node (ref "U8") (pin "M10") (pinfunction "VSS_M10") (pintype "power_in"))
      (node (ref "U8") (pin "M11") (pinfunction "VSS_M11") (pintype "power_in"))
      (node (ref "U8") (pin "M12") (pinfunction "VSS_M12") (pintype "power_in"))
      (node (ref "U8") (pin "M14") (pinfunction "VSS_M14") (pintype "power_in"))
      (node (ref "U8") (pin "M15") (pinfunction "VSS_M15") (pintype "power_in"))
      (node (ref "U8") (pin "M8") (pinfunction "VSS_M8") (pintype "power_in"))
      (node (ref "U8") (pin "M9") (pinfunction "VSS_M9") (pintype "power_in"))
      (node (ref "U8") (pin "N1") (pinfunction "VSS_N1") (pintype "power_in"))
      (node (ref "U8") (pin "N5") (pinfunction "VSS_N5") (pintype "power_in"))
      (node (ref "U8") (pin "N6") (pinfunction "VSS_N6") (pintype "power_in"))
      (node (ref "U8") (pin "P11") (pinfunction "VSS_P11") (pintype "power_in"))
      (node (ref "U8") (pin "P12") (pinfunction "VSS_P12") (pintype "power_in"))
      (node (ref "U8") (pin "P14") (pinfunction "VSS_P14") (pintype "power_in"))
      (node (ref "U8") (pin "P15") (pinfunction "VSS_P15") (pintype "power_in"))
      (node (ref "U8") (pin "P7") (pinfunction "VSS_P7") (pintype "power_in"))
      (node (ref "U8") (pin "P8") (pinfunction "VSS_P8") (pintype "power_in"))
      (node (ref "U8") (pin "R14") (pinfunction "VSS_R14") (pintype "power_in"))
      (node (ref "U8") (pin "R15") (pinfunction "VSS_R15") (pintype "power_in"))
      (node (ref "U8") (pin "R7") (pinfunction "VSS_R7") (pintype "power_in"))
      (node (ref "U8") (pin "R8") (pinfunction "VSS_R8") (pintype "power_in"))
      (node (ref "U8") (pin "W19") (pinfunction "VSS_W19") (pintype "power_in"))
      (node (ref "U8") (pin "W7") (pinfunction "VSS_W7") (pintype "power_in"))
    )
    (net (code "8") (name "Net-(C112-Pad2)") (class "Default")
      (node (ref "C112") (pin "2") (pinfunction "2_2") (pintype "passive"))
      (node (ref "C22") (pin "1") (pinfunction "1_1") (pintype "passive"))
      (node (ref "R12") (pin "1") (pinfunction "1_1") (pintype "passive"))
      (node (ref "U1") (pin "10") (pinfunction "FB/OUT_10") (pintype "passive"))
      (node (ref "U1") (pin "9") (pinfunction "FB/OUT_9") (pintype "passive"))
    )
    (net (code "9") (name "Net-(D1-PadA)") (class "Default")
      (node (ref "D1") (pin "A") (pinfunction "A_A") (pintype "passive"))
      (node (ref "R7") (pin "1") (pinfunction "1_1") (pintype "passive"))
    )
    (net (code "10") (name "Net-(R16-Pad2)") (class "Default")
      (node (ref "R16") (pin "2") (pinfunction "2_2") (pintype "passive"))
      (node (ref "R9") (pin "1") (pinfunction "1_1") (pintype "passive"))
    )
    (net (code "11") (name "Net-(U1-BIAS)") (class "Default")
      (node (ref "R8") (pin "1") (pinfunction "1_1") (pintype "passive"))
      (node (ref "U1") (pin "11") (pinfunction "BIAS_11") (pintype "passive"))
    )
    (net (code "12") (name "Net-(U1-BST)") (class "Default")
      (node (ref "C17") (pin "2") (pinfunction "2_2") (pintype "passive"))
      (node (ref "U1") (pin "14") (pinfunction "BST_14") (pintype "passive"))
    )
    (net (code "13") (name "Net-(U1-INTVcc)") (class "Default")
      (node (ref "C18") (pin "2") (pinfunction "2_2") (pintype "passive"))
      (node (ref "U1") (pin "12") (pinfunction "INTVcc_12") (pintype "passive"))
    )
    (net (code "14") (name "Net-(U1-RT)") (class "Default")
      (node (ref "R10") (pin "2") (pinfunction "2_2") (pintype "passive"))
      (node (ref "U1") (pin "5") (pinfunction "RT_5") (pintype "passive"))
    )
    (net (code "15") (name "Net-(U2-ADJ2)") (class "Default")
      (node (ref "C10") (pin "1") (pinfunction "1_1") (pintype "passive"))
      (node (ref "R1") (pin "2") (pinfunction "2_2") (pintype "passive"))
      (node (ref "R2") (pin "1") (pinfunction "1_1") (pintype "passive"))
      (node (ref "U2") (pin "1") (pinfunction "ADJ2_1") (pintype "input"))
    )
    (net (code "16") (name "Net-(U2-DEF_1)") (class "Default")
      (node (ref "R15") (pin "2") (pinfunction "2_2") (pintype "passive"))
      (node (ref "R16") (pin "1") (pinfunction "1_1") (pintype "passive"))
      (node (ref "U2") (pin "5") (pinfunction "DEF_1_5") (pintype "input"))
    )
    (net (code "17") (name "Net-(U2-EN1)") (class "Default")
      (node (ref "C23") (pin "2") (pinfunction "2_2") (pintype "passive"))
      (node (ref "R13") (pin "1") (pinfunction "1_1") (pintype "passive"))
      (node (ref "U2") (pin "7") (pinfunction "EN1_7") (pintype "input"))
    )
    (net (code "18") (name "Net-(U2-EN2)") (class "Default")
      (node (ref "C15") (pin "2") (pinfunction "2_2") (pintype "passive"))
      (node (ref "R4") (pin "1") (pinfunction "1_1") (pintype "passive"))
      (node (ref "U2") (pin "9") (pinfunction "EN2_9") (pintype "input"))
    )
    (net (code "19") (name "Net-(U2-FB1)") (class "Default")
      (node (ref "R17") (pin "1") (pinfunction "1_1") (pintype "passive"))
      (node (ref "U2") (pin "4") (pinfunction "FB1_4") (pintype "input"))
    )
    (net (code "20") (name "Net-(U2-MODE{slash}DATA)") (class "Default")
      (node (ref "R5") (pin "2") (pinfunction "2_2") (pintype "passive"))
      (node (ref "R6") (pin "1") (pinfunction "1_1") (pintype "passive"))
      (node (ref "U2") (pin "2") (pinfunction "MODE/DATA_2") (pintype "bidirectional"))
    )
    (net (code "21") (name "Net-(U2-SW1)") (class "Default")
      (node (ref "L3") (pin "1") (pinfunction "1_1") (pintype "passive"))
      (node (ref "U2") (pin "6") (pinfunction "SW1_6") (pintype "power_in"))
    )
    (net (code "22") (name "Net-(U2-SW2)") (class "Default")
      (node (ref "L2") (pin "1") (pinfunction "1_1") (pintype "passive"))
      (node (ref "U2") (pin "10") (pinfunction "SW2_10") (pintype "power_in"))
    )
    (net (code "23") (name "VDDA_3V3") (class "Default")
      (node (ref "C108") (pin "2") (pinfunction "2_2") (pintype "passive"))
      (node (ref "C96") (pin "2") (pinfunction "2_2") (pintype "passive"))
      (node (ref "C98") (pin "2") (pinfunction "2_2") (pintype "passive"))
      (node (ref "FB3") (pin "2") (pinfunction "2_2") (pintype "passive"))
      (node (ref "U8") (pin "P6") (pinfunction "VDDA_P6") (pintype "power_in"))
      (node (ref "U8") (pin "R6") (pinfunction "VDDA_R6") (pintype "power_in"))
    )
    (net (code "24") (name "VDD_1V2") (class "Default")
      (node (ref "C76") (pin "2") (pinfunction "2_2") (pintype "passive"))
      (node (ref "C79") (pin "2") (pinfunction "2_2") (pintype "passive"))
      (node (ref "C83") (pin "2") (pinfunction "2_2") (pintype "passive"))
      (node (ref "C84") (pin "2") (pinfunction "2_2") (pintype "passive"))
      (node (ref "C90") (pin "2") (pinfunction "2_2") (pintype "passive"))
      (node (ref "C91") (pin "2") (pinfunction "2_2") (pintype "passive"))
      (node (ref "C97") (pin "2") (pinfunction "2_2") (pintype "passive"))
      (node (ref "C99") (pin "2") (pinfunction "2_2") (pintype "passive"))
      (node (ref "FB2") (pin "2") (pinfunction "2_2") (pintype "passive"))
      (node (ref "R97") (pin "2") (pinfunction "2_2") (pintype "passive"))
      (node (ref "U8") (pin "E11") (pinfunction "VDD_E11") (pintype "power_in"))
      (node (ref "U8") (pin "E9") (pinfunction "VDD_E9") (pintype "power_in"))
      (node (ref "U8") (pin "F11") (pinfunction "VDD_F11") (pintype "power_in"))
      (node (ref "U8") (pin "F9") (pinfunction "VDD_F9") (pintype "power_in"))
      (node (ref "U8") (pin "G14") (pinfunction "VDD_G14") (pintype "power_in"))
      (node (ref "U8") (pin "G15") (pinfunction "VDD_G15") (pintype "power_in"))
      (node (ref "U8") (pin "J14") (pinfunction "VDD_J14") (pintype "power_in"))
      (node (ref "U8") (pin "J15") (pinfunction "VDD_J15") (pintype "power_in"))
      (node (ref "U8") (pin "K5") (pinfunction "VDD_K5") (pintype "power_in"))
      (node (ref "U8") (pin "K6") (pinfunction "VDD_K6") (pintype "power_in"))
      (node (ref "U8") (pin "P10") (pinfunction "VDD_P10") (pintype "power_in"))
      (node (ref "U8") (pin "P13") (pinfunction "VDD_P13") (pintype "power_in"))
      (node (ref "U8") (pin "R10") (pinfunction "VDD_R10") (pintype "power_in"))
      (node (ref "U8") (pin "R13") (pinfunction "VDD_R13") (pintype "power_in"))
    )
    (net (code "25") (name "VDD_3V3") (class "Default")
      (node (ref "C103") (pin "2") (pinfunction "2_2") (pintype "passive"))
      (node (ref "C104") (pin "2") (pinfunction "2_2") (pintype "passive"))
      (node (ref "C105") (pin "2") (pinfunction "2_2") (pintype "passive"))
      (node (ref "C74") (pin "2") (pinfunction "2_2") (pintype "passive"))
      (node (ref "C75") (pin "2") (pinfunction "2_2") (pintype "passive"))
      (node (ref "C77") (pin "2") (pinfunction "2_2") (pintype "passive"))
      (node (ref "C78") (pin "2") (pinfunction "2_2") (pintype "passive"))
      (node (ref "C80") (pin "2") (pinfunction "2_2") (pintype "passive"))
      (node (ref "C82") (pin "2") (pinfunction "2_2") (pintype "passive"))
      (node (ref "C85") (pin "2") (pinfunction "2_2") (pintype "passive"))
      (node (ref "C86") (pin "2") (pinfunction "2_2") (pintype "passive"))
      (node (ref "C87") (pin "2") (pinfunction "2_2") (pintype "passive"))
      (node (ref "C88") (pin "2") (pinfunction "2_2") (pintype "passive"))
      (node (ref "C89") (pin "2") (pinfunction "2_2") (pintype "passive"))
      (node (ref "C92") (pin "2") (pinfunction "2_2") (pintype "passive"))
      (node (ref "C93") (pin "2") (pinfunction "2_2") (pintype "passive"))
      (node (ref "C94") (pin "2") (pinfunction "2_2") (pintype "passive"))
      (node (ref "FB1") (pin "2") (pinfunction "2_2") (pintype "passive"))
      (node (ref "U8") (pin "A18") (pinfunction "VDDIO_A18") (pintype "power_in"))
      (node (ref "U8") (pin "A9") (pinfunction "VDDIO_A9") (pintype "power_in"))
      (node (ref "U8") (pin "B1") (pinfunction "VDDIO_B1") (pintype "power_in"))
      (node (ref "U8") (pin "E10") (pinfunction "VDDIO_E10") (pintype "power_in"))
      (node (ref "U8") (pin "E13") (pinfunction "VDDIO_E13") (pintype "power_in"))
      (node (ref "U8") (pin "E16") (pinfunction "VDDIO_E16") (pintype "power_in"))
      (node (ref "U8") (pin "E7") (pinfunction "VDDIO_E7") (pintype "power_in"))
      (node (ref "U8") (pin "F10") (pinfunction "VDDIO_F10") (pintype "power_in"))
      (node (ref "U8") (pin "F13") (pinfunction "VDDIO_F13") (pintype "power_in"))
      (node (ref "U8") (pin "F16") (pinfunction "VDDIO_F16") (pintype "power_in"))
      (node (ref "U8") (pin "F4") (pinfunction "VDDIO_F4") (pintype "power_in"))
      (node (ref "U8") (pin "F7") (pinfunction "VDDIO_F7") (pintype "power_in"))
      (node (ref "U8") (pin "G4") (pinfunction "VDDIO_G4") (pintype "power_in"))
      (node (ref "U8") (pin "G5") (pinfunction "VDDIO_G5") (pintype "power_in"))
      (node (ref "U8") (pin "G6") (pinfunction "VDDIO_G6") (pintype "power_in"))
      (node (ref "U8") (pin "H16") (pinfunction "VDDOSC_H16") (pintype "power_in"))
      (node (ref "U8") (pin "H17") (pinfunction "VDDOSC_H17") (pintype "power_in"))
      (node (ref "U8") (pin "H5") (pinfunction "VDDIO_H5") (pintype "power_in"))
      (node (ref "U8") (pin "H6") (pinfunction "VDDIO_H6") (pintype "power_in"))
      (node (ref "U8") (pin "L14") (pinfunction "VDDIO_L14") (pintype "power_in"))
      (node (ref "U8") (pin "L15") (pinfunction "VDDIO_L15") (pintype "power_in"))
      (node (ref "U8") (pin "M1") (pinfunction "VDDIO_M1") (pintype "power_in"))
      (node (ref "U8") (pin "M5") (pinfunction "VDDIO_M5") (pintype "power_in"))
      (node (ref "U8") (pin "M6") (pinfunction "VDDIO_M6") (pintype "power_in"))
      (node (ref "U8") (pin "N14") (pinfunction "VDDIO_N14") (pintype "power_in"))
      (node (ref "U8") (pin "N15") (pinfunction "VDDIO_N15") (pintype "power_in"))
      (node (ref "U8") (pin "P9") (pinfunction "VDDIO_P9") (pintype "power_in"))
      (node (ref "U8") (pin "R11") (pinfunction "VDD3VFL_R11") (pintype "power_in"))
      (node (ref "U8") (pin "R12") (pinfunction "VDD3VFL_R12") (pintype "power_in"))
      (node (ref "U8") (pin "R9") (pinfunction "VDDIO_R9") (pintype "power_in"))
      (node (ref "U8") (pin "V19") (pinfunction "VDDIO_V19") (pintype "power_in"))
      (node (ref "U8") (pin "W8") (pinfunction "VDDIO_W8") (pintype "power_in"))
    )
    (net (code "26") (name "VIN_48V") (class "Default")
      (node (ref "C12") (pin "2") (pinfunction "2_2") (pintype "passive"))
      (node (ref "C14") (pin "2") (pinfunction "2_2") (pintype "passive"))
      (node (ref "C9") (pin "2") (pinfunction "2_2") (pintype "passive"))
      (node (ref "R3") (pin "2") (pinfunction "2_2") (pintype "passive"))
      (node (ref "U1") (pin "2") (pinfunction "VIN_2") (pintype "passive"))
    )
    (net (code "27") (name "unconnected-(U1-PG-Pad6)") (class "Default")
      (node (ref "U1") (pin "6") (pinfunction "PG_6") (pintype "passive"))
    )
  )
)
